# Buzzer_22-23.net
KiCad netlist of a schematic drawn in Altium Designer
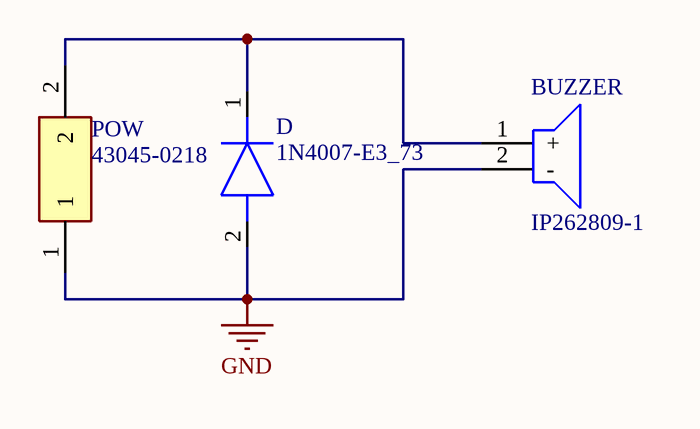
[diagram p0: Buzzer_22-23.SchDoc]

(export (version "E")
  (design (tool "Eeschema 10.0.6"))
  (components
    (comp (ref "BUZZER")
      (value "IP262809-1")
      (footprint "SamacSys:IP2628091")
      (description "Loudspeaker or Buzzer")
      (fields (field (name "MOUSER PART NUMBER") "497-IP262809-1"))
      (libsource (lib "*") (part "IP262809-1"))
    )
    (comp (ref "D")
      (value "1N4007-E3_73")
      (footprint "SamacSys:DIOAD1405W86L465D235")
      (description "Diode")
      (fields
        (field (name "MANUFACTURER_PART_NUMBER") "1N4007-E3/73")
        (field (name "MOUSER PART NUMBER") "625-1N4007-E3/73")
      )
      (libsource (lib "*") (part "1N4007-E3_73"))
    )
    (comp (ref "POW")
      (value "43045-0218")
      (footprint "SamacSys:43045-02YY_181920")
      (description "Connector")
      (fields (field (name "MOUSER PART NUMBER") "538-43045-0218"))
      (libsource (lib "SamacSys") (part "43045-0218"))
    )
  )
  (nets
    (net (code "1") (name "GND") (class "Default")
      (node (ref "BUZZER") (pin "2") (pinfunction "-_2") (pintype "passive"))
      (node (ref "D") (pin "2") (pinfunction "A_2") (pintype "passive"))
      (node (ref "POW") (pin "1") (pinfunction "1_1") (pintype "passive"))
    )
    (net (code "2") (name "Net-(BUZZER-+)") (class "Default")
      (node (ref "BUZZER") (pin "1") (pinfunction "+_1") (pintype "passive"))
      (node (ref "D") (pin "1") (pinfunction "K_1") (pintype "passive"))
      (node (ref "POW") (pin "2") (pinfunction "2_2") (pintype "passive"))
    )
  )
)
